# Kasli-SOC_bank33-34-35.net
KiCad netlist of a schematic drawn in Altium Designer
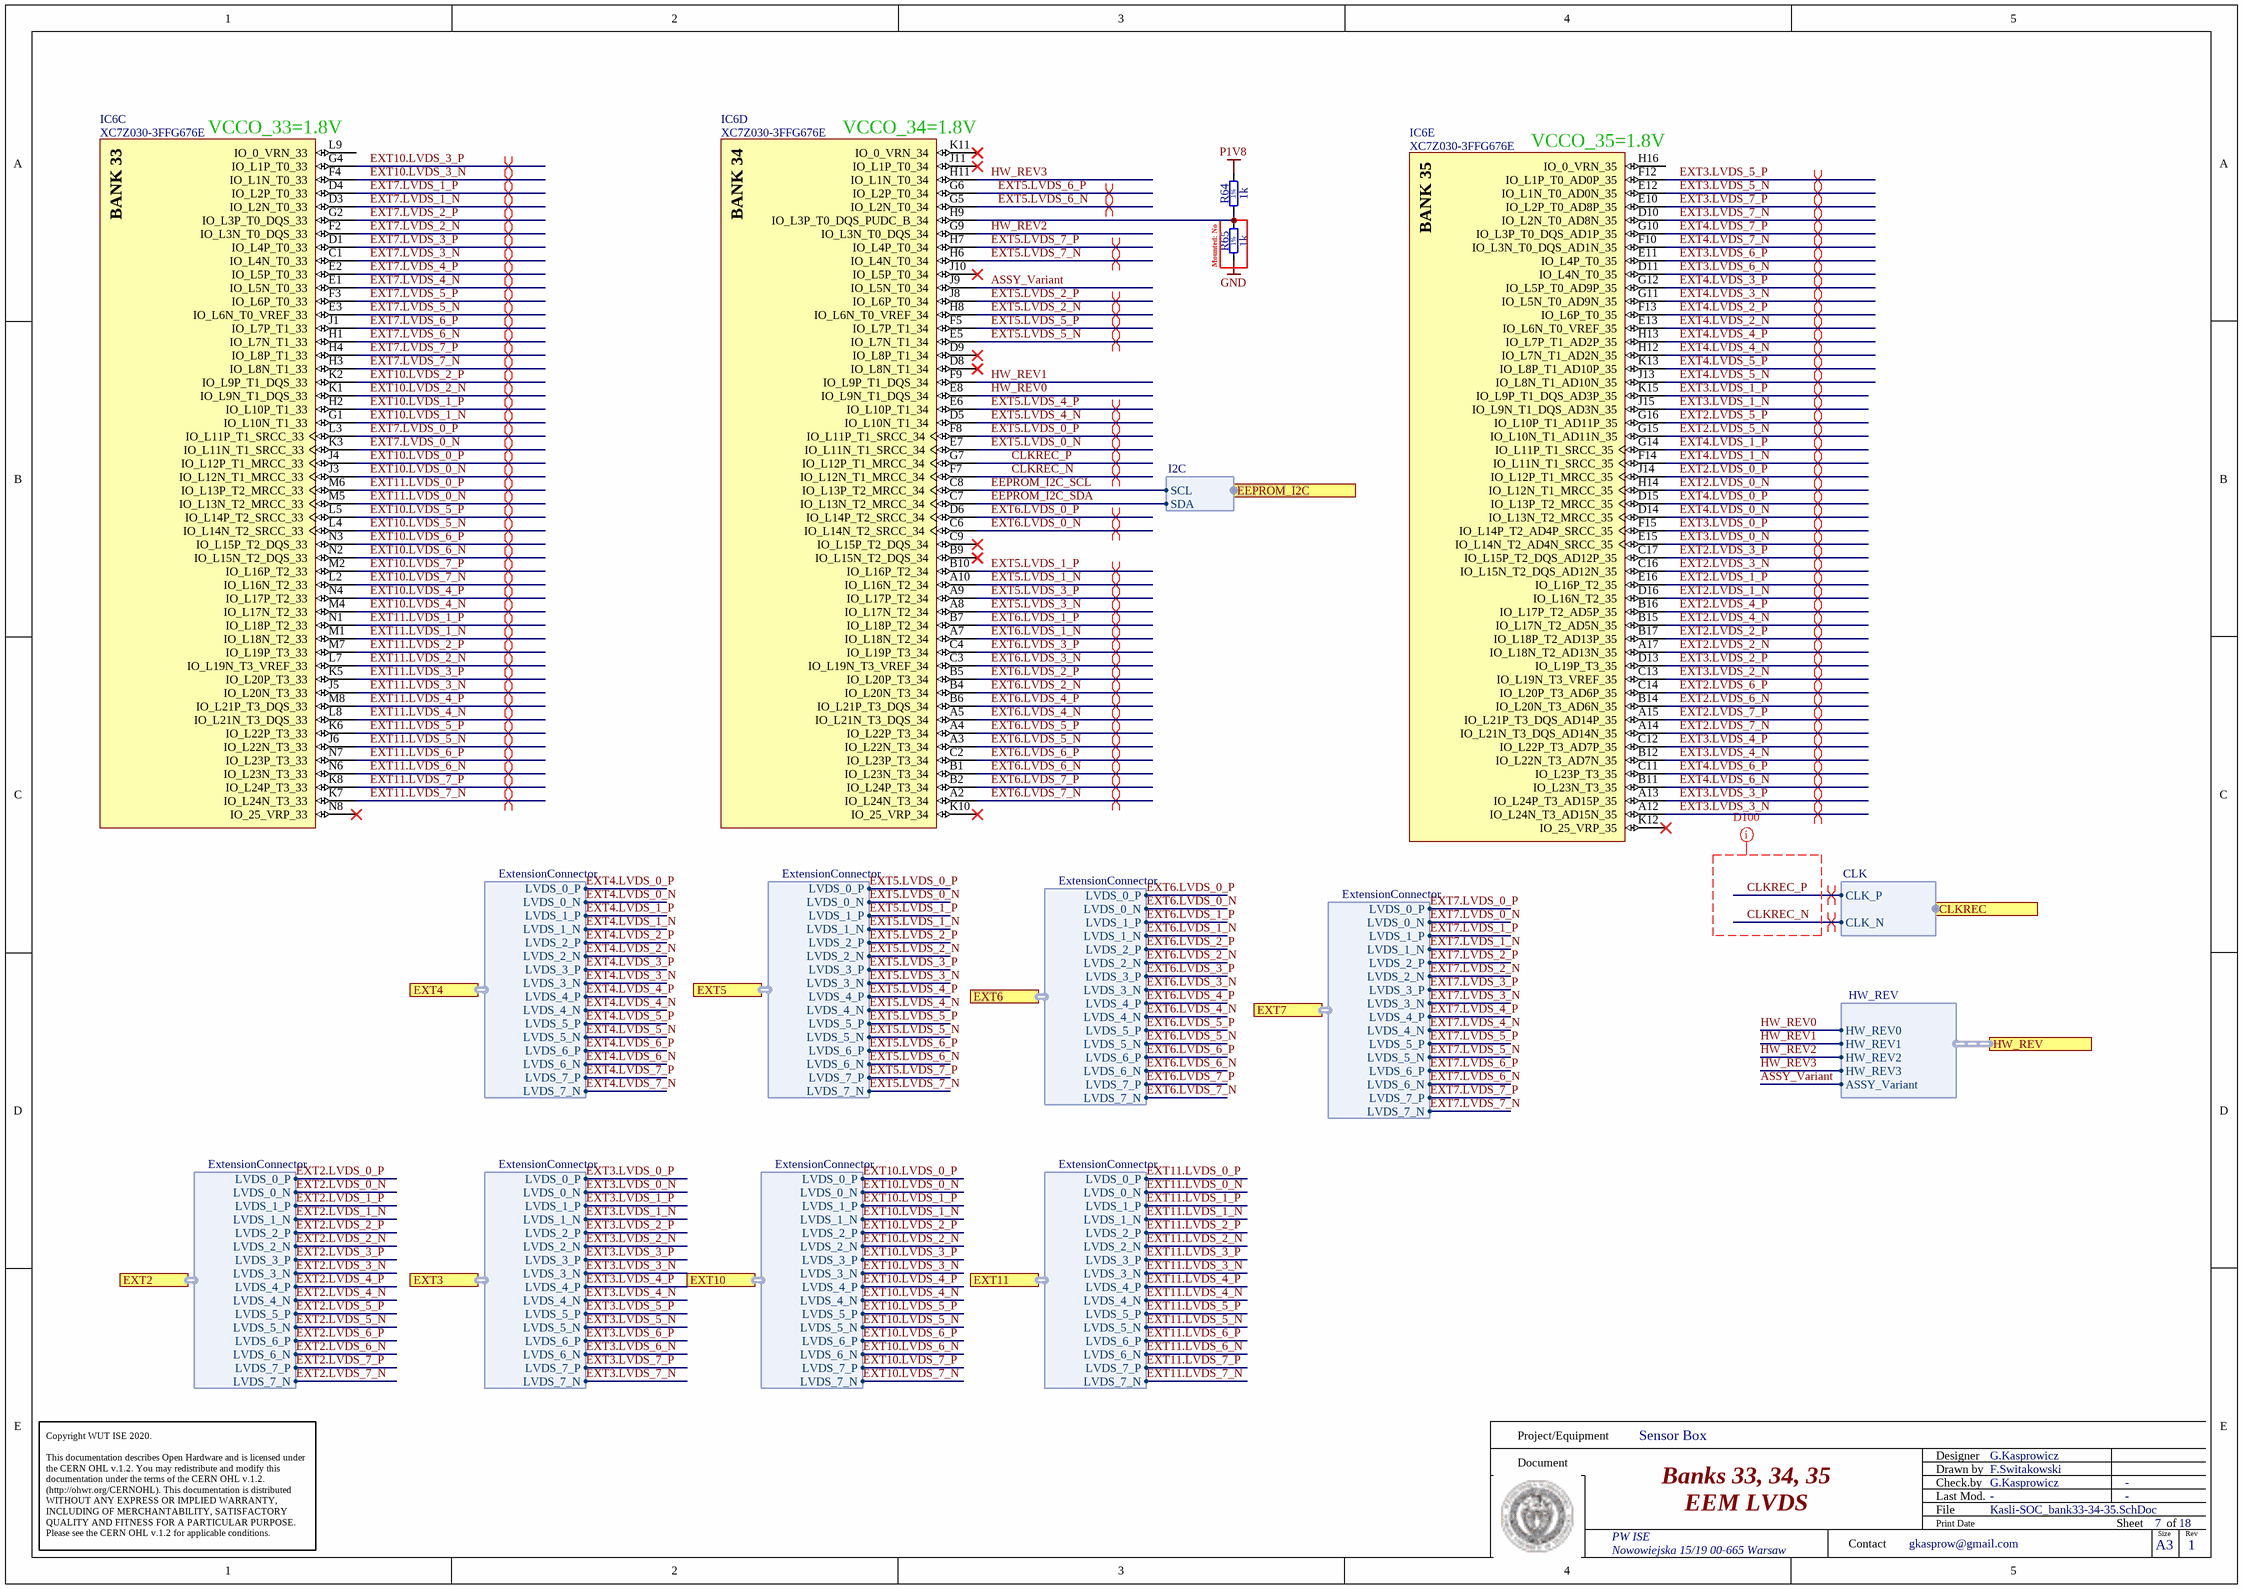
[diagram p0: Kasli-SOC_bank33-34-35.SchDoc]

(export (version "E")
  (design (tool "Eeschema 10.0.6"))
  (components
    (comp (ref "IC6")
      (value "XC7Z030-3FFG676E")
      (footprint "BGA676C100P26X26_2700X2700X324")
      (fields (field (name "MANUFACTURER") "XILINX") (field (name "AUTHOR") "CERN DEM JLC"))
      (libsource (lib "ICs And Semiconductors") (part "XC7Z030-2FFG676I"))
    )
    (comp (ref "R64")
      (value "1k")
      (footprint "RESC1005X40N")
      (description "Resistor - 1%")
      (fields
        (field (name "PART NUMBER") "R0402_1K_1%_0.0625W_100PPM")
        (field (name "POWER") "0.0625W")
        (field (name "AUTHOR") "CERN DEM JLC")
      )
      (libsource (lib "Resistors") (part "Resistor - 1%"))
    )
    (comp (ref "R65")
      (value "1k")
      (footprint "RESC1005X40N")
      (description "Resistor - 1%")
      (fields
        (field (name "PART NUMBER") "R0402_1K_1%_0.0625W_100PPM")
        (field (name "POWER") "0.0625W")
        (field (name "AUTHOR") "CERN DEM JLC")
      )
      (libsource (lib "Resistors") (part "Resistor - 1%"))
    )
  )
  (nets
    (net (code "5") (name "/ASSY_Variant") (class "Default")
      (node (ref "IC6") (pin "J9") (pinfunction "IO_L5N_T0_34_J9") (pintype "bidirectional"))
    )
    (net (code "6") (name "/CLKREC_N") (class "Default")
      (node (ref "IC6") (pin "F7") (pinfunction "IO_L12N_T1_MRCC_34_F7") (pintype "bidirectional"))
    )
    (net (code "7") (name "/CLKREC_P") (class "Default")
      (node (ref "IC6") (pin "G7") (pinfunction "IO_L12P_T1_MRCC_34_G7") (pintype "bidirectional"))
    )
    (net (code "8") (name "/EEPROM_I2C_SCL") (class "Default")
      (node (ref "IC6") (pin "C8") (pinfunction "IO_L13P_T2_MRCC_34_C8") (pintype "bidirectional"))
    )
    (net (code "9") (name "/EEPROM_I2C_SDA") (class "Default")
      (node (ref "IC6") (pin "C7") (pinfunction "IO_L13N_T2_MRCC_34_C7") (pintype "bidirectional"))
    )
    (net (code "10") (name "/EXT2.LVDS_0_N") (class "Default")
      (node (ref "IC6") (pin "H14") (pinfunction "IO_L12N_T1_MRCC_35_H14") (pintype "bidirectional"))
    )
    (net (code "11") (name "/EXT2.LVDS_0_P") (class "Default")
      (node (ref "IC6") (pin "J14") (pinfunction "IO_L12P_T1_MRCC_35_J14") (pintype "bidirectional"))
    )
    (net (code "12") (name "/EXT2.LVDS_1_N") (class "Default")
      (node (ref "IC6") (pin "D16") (pinfunction "IO_L16N_T2_35_D16") (pintype "bidirectional"))
    )
    (net (code "13") (name "/EXT2.LVDS_1_P") (class "Default")
      (node (ref "IC6") (pin "E16") (pinfunction "IO_L16P_T2_35_E16") (pintype "bidirectional"))
    )
    (net (code "14") (name "/EXT2.LVDS_2_N") (class "Default")
      (node (ref "IC6") (pin "A17") (pinfunction "IO_L18N_T2_AD13N_35_A17") (pintype "bidirectional"))
    )
    (net (code "15") (name "/EXT2.LVDS_2_P") (class "Default")
      (node (ref "IC6") (pin "B17") (pinfunction "IO_L18P_T2_AD13P_35_B17") (pintype "bidirectional"))
    )
    (net (code "16") (name "/EXT2.LVDS_3_N") (class "Default")
      (node (ref "IC6") (pin "C16") (pinfunction "IO_L15N_T2_DQS_AD12N_35_C16") (pintype "bidirectional"))
    )
    (net (code "17") (name "/EXT2.LVDS_3_P") (class "Default")
      (node (ref "IC6") (pin "C17") (pinfunction "IO_L15P_T2_DQS_AD12P_35_C17") (pintype "bidirectional"))
    )
    (net (code "18") (name "/EXT2.LVDS_4_N") (class "Default")
      (node (ref "IC6") (pin "B15") (pinfunction "IO_L17N_T2_AD5N_35_B15") (pintype "bidirectional"))
    )
    (net (code "19") (name "/EXT2.LVDS_4_P") (class "Default")
      (node (ref "IC6") (pin "B16") (pinfunction "IO_L17P_T2_AD5P_35_B16") (pintype "bidirectional"))
    )
    (net (code "20") (name "/EXT2.LVDS_5_N") (class "Default")
      (node (ref "IC6") (pin "G15") (pinfunction "IO_L10N_T1_AD11N_35_G15") (pintype "bidirectional"))
    )
    (net (code "21") (name "/EXT2.LVDS_5_P") (class "Default")
      (node (ref "IC6") (pin "G16") (pinfunction "IO_L10P_T1_AD11P_35_G16") (pintype "bidirectional"))
    )
    (net (code "22") (name "/EXT2.LVDS_6_N") (class "Default")
      (node (ref "IC6") (pin "B14") (pinfunction "IO_L20N_T3_AD6N_35_B14") (pintype "bidirectional"))
    )
    (net (code "23") (name "/EXT2.LVDS_6_P") (class "Default")
      (node (ref "IC6") (pin "C14") (pinfunction "IO_L20P_T3_AD6P_35_C14") (pintype "bidirectional"))
    )
    (net (code "24") (name "/EXT2.LVDS_7_N") (class "Default")
      (node (ref "IC6") (pin "A14") (pinfunction "IO_L21N_T3_DQS_AD14N_35_A14") (pintype "bidirectional"))
    )
    (net (code "25") (name "/EXT2.LVDS_7_P") (class "Default")
      (node (ref "IC6") (pin "A15") (pinfunction "IO_L21P_T3_DQS_AD14P_35_A15") (pintype "bidirectional"))
    )
    (net (code "26") (name "/EXT3.LVDS_0_N") (class "Default")
      (node (ref "IC6") (pin "E15") (pinfunction "IO_L14N_T2_AD4N_SRCC_35_E15") (pintype "bidirectional"))
    )
    (net (code "27") (name "/EXT3.LVDS_0_P") (class "Default")
      (node (ref "IC6") (pin "F15") (pinfunction "IO_L14P_T2_AD4P_SRCC_35_F15") (pintype "bidirectional"))
    )
    (net (code "28") (name "/EXT3.LVDS_1_N") (class "Default")
      (node (ref "IC6") (pin "J15") (pinfunction "IO_L9N_T1_DQS_AD3N_35_J15") (pintype "bidirectional"))
    )
    (net (code "29") (name "/EXT3.LVDS_1_P") (class "Default")
      (node (ref "IC6") (pin "K15") (pinfunction "IO_L9P_T1_DQS_AD3P_35_K15") (pintype "bidirectional"))
    )
    (net (code "30") (name "/EXT3.LVDS_2_N") (class "Default")
      (node (ref "IC6") (pin "C13") (pinfunction "IO_L19N_T3_VREF_35_C13") (pintype "bidirectional"))
    )
    (net (code "31") (name "/EXT3.LVDS_2_P") (class "Default")
      (node (ref "IC6") (pin "D13") (pinfunction "IO_L19P_T3_35_D13") (pintype "bidirectional"))
    )
    (net (code "32") (name "/EXT3.LVDS_3_N") (class "Default")
      (node (ref "IC6") (pin "A12") (pinfunction "IO_L24N_T3_AD15N_35_A12") (pintype "bidirectional"))
    )
    (net (code "33") (name "/EXT3.LVDS_3_P") (class "Default")
      (node (ref "IC6") (pin "A13") (pinfunction "IO_L24P_T3_AD15P_35_A13") (pintype "bidirectional"))
    )
    (net (code "34") (name "/EXT3.LVDS_4_N") (class "Default")
      (node (ref "IC6") (pin "B12") (pinfunction "IO_L22N_T3_AD7N_35_B12") (pintype "bidirectional"))
    )
    (net (code "35") (name "/EXT3.LVDS_4_P") (class "Default")
      (node (ref "IC6") (pin "C12") (pinfunction "IO_L22P_T3_AD7P_35_C12") (pintype "bidirectional"))
    )
    (net (code "36") (name "/EXT3.LVDS_5_N") (class "Default")
      (node (ref "IC6") (pin "E12") (pinfunction "IO_L1N_T0_AD0N_35_E12") (pintype "bidirectional"))
    )
    (net (code "37") (name "/EXT3.LVDS_5_P") (class "Default")
      (node (ref "IC6") (pin "F12") (pinfunction "IO_L1P_T0_AD0P_35_F12") (pintype "bidirectional"))
    )
    (net (code "38") (name "/EXT3.LVDS_6_N") (class "Default")
      (node (ref "IC6") (pin "D11") (pinfunction "IO_L4N_T0_35_D11") (pintype "bidirectional"))
    )
    (net (code "39") (name "/EXT3.LVDS_6_P") (class "Default")
      (node (ref "IC6") (pin "E11") (pinfunction "IO_L4P_T0_35_E11") (pintype "bidirectional"))
    )
    (net (code "40") (name "/EXT3.LVDS_7_N") (class "Default")
      (node (ref "IC6") (pin "D10") (pinfunction "IO_L2N_T0_AD8N_35_D10") (pintype "bidirectional"))
    )
    (net (code "41") (name "/EXT3.LVDS_7_P") (class "Default")
      (node (ref "IC6") (pin "E10") (pinfunction "IO_L2P_T0_AD8P_35_E10") (pintype "bidirectional"))
    )
    (net (code "42") (name "/EXT4.LVDS_0_N") (class "Default")
      (node (ref "IC6") (pin "D14") (pinfunction "IO_L13N_T2_MRCC_35_D14") (pintype "bidirectional"))
    )
    (net (code "43") (name "/EXT4.LVDS_0_P") (class "Default")
      (node (ref "IC6") (pin "D15") (pinfunction "IO_L13P_T2_MRCC_35_D15") (pintype "bidirectional"))
    )
    (net (code "44") (name "/EXT4.LVDS_1_N") (class "Default")
      (node (ref "IC6") (pin "F14") (pinfunction "IO_L11N_T1_SRCC_35_F14") (pintype "bidirectional"))
    )
    (net (code "45") (name "/EXT4.LVDS_1_P") (class "Default")
      (node (ref "IC6") (pin "G14") (pinfunction "IO_L11P_T1_SRCC_35_G14") (pintype "bidirectional"))
    )
    (net (code "46") (name "/EXT4.LVDS_2_N") (class "Default")
      (node (ref "IC6") (pin "E13") (pinfunction "IO_L6N_T0_VREF_35_E13") (pintype "bidirectional"))
    )
    (net (code "47") (name "/EXT4.LVDS_2_P") (class "Default")
      (node (ref "IC6") (pin "F13") (pinfunction "IO_L6P_T0_35_F13") (pintype "bidirectional"))
    )
    (net (code "48") (name "/EXT4.LVDS_3_N") (class "Default")
      (node (ref "IC6") (pin "G11") (pinfunction "IO_L5N_T0_AD9N_35_G11") (pintype "bidirectional"))
    )
    (net (code "49") (name "/EXT4.LVDS_3_P") (class "Default")
      (node (ref "IC6") (pin "G12") (pinfunction "IO_L5P_T0_AD9P_35_G12") (pintype "bidirectional"))
    )
    (net (code "50") (name "/EXT4.LVDS_4_N") (class "Default")
      (node (ref "IC6") (pin "H12") (pinfunction "IO_L7N_T1_AD2N_35_H12") (pintype "bidirectional"))
    )
    (net (code "51") (name "/EXT4.LVDS_4_P") (class "Default")
      (node (ref "IC6") (pin "H13") (pinfunction "IO_L7P_T1_AD2P_35_H13") (pintype "bidirectional"))
    )
    (net (code "52") (name "/EXT4.LVDS_5_N") (class "Default")
      (node (ref "IC6") (pin "J13") (pinfunction "IO_L8N_T1_AD10N_35_J13") (pintype "bidirectional"))
    )
    (net (code "53") (name "/EXT4.LVDS_5_P") (class "Default")
      (node (ref "IC6") (pin "K13") (pinfunction "IO_L8P_T1_AD10P_35_K13") (pintype "bidirectional"))
    )
    (net (code "54") (name "/EXT4.LVDS_6_N") (class "Default")
      (node (ref "IC6") (pin "B11") (pinfunction "IO_L23N_T3_35_B11") (pintype "bidirectional"))
    )
    (net (code "55") (name "/EXT4.LVDS_6_P") (class "Default")
      (node (ref "IC6") (pin "C11") (pinfunction "IO_L23P_T3_35_C11") (pintype "bidirectional"))
    )
    (net (code "56") (name "/EXT4.LVDS_7_N") (class "Default")
      (node (ref "IC6") (pin "F10") (pinfunction "IO_L3N_T0_DQS_AD1N_35_F10") (pintype "bidirectional"))
    )
    (net (code "57") (name "/EXT4.LVDS_7_P") (class "Default")
      (node (ref "IC6") (pin "G10") (pinfunction "IO_L3P_T0_DQS_AD1P_35_G10") (pintype "bidirectional"))
    )
    (net (code "58") (name "/EXT5.LVDS_0_N") (class "Default")
      (node (ref "IC6") (pin "E7") (pinfunction "IO_L11N_T1_SRCC_34_E7") (pintype "bidirectional"))
    )
    (net (code "59") (name "/EXT5.LVDS_0_P") (class "Default")
      (node (ref "IC6") (pin "F8") (pinfunction "IO_L11P_T1_SRCC_34_F8") (pintype "bidirectional"))
    )
    (net (code "60") (name "/EXT5.LVDS_1_N") (class "Default")
      (node (ref "IC6") (pin "A10") (pinfunction "IO_L16N_T2_34_A10") (pintype "bidirectional"))
    )
    (net (code "61") (name "/EXT5.LVDS_1_P") (class "Default")
      (node (ref "IC6") (pin "B10") (pinfunction "IO_L16P_T2_34_B10") (pintype "bidirectional"))
    )
    (net (code "62") (name "/EXT5.LVDS_2_N") (class "Default")
      (node (ref "IC6") (pin "H8") (pinfunction "IO_L6N_T0_VREF_34_H8") (pintype "bidirectional"))
    )
    (net (code "63") (name "/EXT5.LVDS_2_P") (class "Default")
      (node (ref "IC6") (pin "J8") (pinfunction "IO_L6P_T0_34_J8") (pintype "bidirectional"))
    )
    (net (code "64") (name "/EXT5.LVDS_3_N") (class "Default")
      (node (ref "IC6") (pin "A8") (pinfunction "IO_L17N_T2_34_A8") (pintype "bidirectional"))
    )
    (net (code "65") (name "/EXT5.LVDS_3_P") (class "Default")
      (node (ref "IC6") (pin "A9") (pinfunction "IO_L17P_T2_34_A9") (pintype "bidirectional"))
    )
    (net (code "66") (name "/EXT5.LVDS_4_N") (class "Default")
      (node (ref "IC6") (pin "D5") (pinfunction "IO_L10N_T1_34_D5") (pintype "bidirectional"))
    )
    (net (code "67") (name "/EXT5.LVDS_4_P") (class "Default")
      (node (ref "IC6") (pin "E6") (pinfunction "IO_L10P_T1_34_E6") (pintype "bidirectional"))
    )
    (net (code "68") (name "/EXT5.LVDS_5_N") (class "Default")
      (node (ref "IC6") (pin "E5") (pinfunction "IO_L7N_T1_34_E5") (pintype "bidirectional"))
    )
    (net (code "69") (name "/EXT5.LVDS_5_P") (class "Default")
      (node (ref "IC6") (pin "F5") (pinfunction "IO_L7P_T1_34_F5") (pintype "bidirectional"))
    )
    (net (code "70") (name "/EXT5.LVDS_6_N") (class "Default")
      (node (ref "IC6") (pin "G5") (pinfunction "IO_L2N_T0_34_G5") (pintype "bidirectional"))
    )
    (net (code "71") (name "/EXT5.LVDS_6_P") (class "Default")
      (node (ref "IC6") (pin "G6") (pinfunction "IO_L2P_T0_34_G6") (pintype "bidirectional"))
    )
    (net (code "72") (name "/EXT5.LVDS_7_N") (class "Default")
      (node (ref "IC6") (pin "H6") (pinfunction "IO_L4N_T0_34_H6") (pintype "bidirectional"))
    )
    (net (code "73") (name "/EXT5.LVDS_7_P") (class "Default")
      (node (ref "IC6") (pin "H7") (pinfunction "IO_L4P_T0_34_H7") (pintype "bidirectional"))
    )
    (net (code "74") (name "/EXT6.LVDS_0_N") (class "Default")
      (node (ref "IC6") (pin "C6") (pinfunction "IO_L14N_T2_SRCC_34_C6") (pintype "bidirectional"))
    )
    (net (code "75") (name "/EXT6.LVDS_0_P") (class "Default")
      (node (ref "IC6") (pin "D6") (pinfunction "IO_L14P_T2_SRCC_34_D6") (pintype "bidirectional"))
    )
    (net (code "76") (name "/EXT6.LVDS_1_N") (class "Default")
      (node (ref "IC6") (pin "A7") (pinfunction "IO_L18N_T2_34_A7") (pintype "bidirectional"))
    )
    (net (code "77") (name "/EXT6.LVDS_1_P") (class "Default")
      (node (ref "IC6") (pin "B7") (pinfunction "IO_L18P_T2_34_B7") (pintype "bidirectional"))
    )
    (net (code "78") (name "/EXT6.LVDS_2_N") (class "Default")
      (node (ref "IC6") (pin "B4") (pinfunction "IO_L20N_T3_34_B4") (pintype "bidirectional"))
    )
    (net (code "79") (name "/EXT6.LVDS_2_P") (class "Default")
      (node (ref "IC6") (pin "B5") (pinfunction "IO_L20P_T3_34_B5") (pintype "bidirectional"))
    )
    (net (code "80") (name "/EXT6.LVDS_3_N") (class "Default")
      (node (ref "IC6") (pin "C3") (pinfunction "IO_L19N_T3_VREF_34_C3") (pintype "bidirectional"))
    )
    (net (code "81") (name "/EXT6.LVDS_3_P") (class "Default")
      (node (ref "IC6") (pin "C4") (pinfunction "IO_L19P_T3_34_C4") (pintype "bidirectional"))
    )
    (net (code "82") (name "/EXT6.LVDS_4_N") (class "Default")
      (node (ref "IC6") (pin "A5") (pinfunction "IO_L21N_T3_DQS_34_A5") (pintype "bidirectional"))
    )
    (net (code "83") (name "/EXT6.LVDS_4_P") (class "Default")
      (node (ref "IC6") (pin "B6") (pinfunction "IO_L21P_T3_DQS_34_B6") (pintype "bidirectional"))
    )
    (net (code "84") (name "/EXT6.LVDS_5_N") (class "Default")
      (node (ref "IC6") (pin "A3") (pinfunction "IO_L22N_T3_34_A3") (pintype "bidirectional"))
    )
    (net (code "85") (name "/EXT6.LVDS_5_P") (class "Default")
      (node (ref "IC6") (pin "A4") (pinfunction "IO_L22P_T3_34_A4") (pintype "bidirectional"))
    )
    (net (code "86") (name "/EXT6.LVDS_6_N") (class "Default")
      (node (ref "IC6") (pin "B1") (pinfunction "IO_L23N_T3_34_B1") (pintype "bidirectional"))
    )
    (net (code "87") (name "/EXT6.LVDS_6_P") (class "Default")
      (node (ref "IC6") (pin "C2") (pinfunction "IO_L23P_T3_34_C2") (pintype "bidirectional"))
    )
    (net (code "88") (name "/EXT6.LVDS_7_N") (class "Default")
      (node (ref "IC6") (pin "A2") (pinfunction "IO_L24N_T3_34_A2") (pintype "bidirectional"))
    )
    (net (code "89") (name "/EXT6.LVDS_7_P") (class "Default")
      (node (ref "IC6") (pin "B2") (pinfunction "IO_L24P_T3_34_B2") (pintype "bidirectional"))
    )
    (net (code "90") (name "/EXT7.LVDS_0_N") (class "Default")
      (node (ref "IC6") (pin "K3") (pinfunction "IO_L11N_T1_SRCC_33_K3") (pintype "bidirectional"))
    )
    (net (code "91") (name "/EXT7.LVDS_0_P") (class "Default")
      (node (ref "IC6") (pin "L3") (pinfunction "IO_L11P_T1_SRCC_33_L3") (pintype "bidirectional"))
    )
    (net (code "92") (name "/EXT7.LVDS_1_N") (class "Default")
      (node (ref "IC6") (pin "D3") (pinfunction "IO_L2N_T0_33_D3") (pintype "bidirectional"))
    )
    (net (code "93") (name "/EXT7.LVDS_1_P") (class "Default")
      (node (ref "IC6") (pin "D4") (pinfunction "IO_L2P_T0_33_D4") (pintype "bidirectional"))
    )
    (net (code "94") (name "/EXT7.LVDS_2_N") (class "Default")
      (node (ref "IC6") (pin "F2") (pinfunction "IO_L3N_T0_DQS_33_F2") (pintype "bidirectional"))
    )
    (net (code "95") (name "/EXT7.LVDS_2_P") (class "Default")
      (node (ref "IC6") (pin "G2") (pinfunction "IO_L3P_T0_DQS_33_G2") (pintype "bidirectional"))
    )
    (net (code "96") (name "/EXT7.LVDS_3_N") (class "Default")
      (node (ref "IC6") (pin "C1") (pinfunction "IO_L4N_T0_33_C1") (pintype "bidirectional"))
    )
    (net (code "97") (name "/EXT7.LVDS_3_P") (class "Default")
      (node (ref "IC6") (pin "D1") (pinfunction "IO_L4P_T0_33_D1") (pintype "bidirectional"))
    )
    (net (code "98") (name "/EXT7.LVDS_4_N") (class "Default")
      (node (ref "IC6") (pin "E1") (pinfunction "IO_L5N_T0_33_E1") (pintype "bidirectional"))
    )
    (net (code "99") (name "/EXT7.LVDS_4_P") (class "Default")
      (node (ref "IC6") (pin "E2") (pinfunction "IO_L5P_T0_33_E2") (pintype "bidirectional"))
    )
    (net (code "100") (name "/EXT7.LVDS_5_N") (class "Default")
      (node (ref "IC6") (pin "E3") (pinfunction "IO_L6N_T0_VREF_33_E3") (pintype "bidirectional"))
    )
    (net (code "101") (name "/EXT7.LVDS_5_P") (class "Default")
      (node (ref "IC6") (pin "F3") (pinfunction "IO_L6P_T0_33_F3") (pintype "bidirectional"))
    )
    (net (code "102") (name "/EXT7.LVDS_6_N") (class "Default")
      (node (ref "IC6") (pin "H1") (pinfunction "IO_L7N_T1_33_H1") (pintype "bidirectional"))
    )
    (net (code "103") (name "/EXT7.LVDS_6_P") (class "Default")
      (node (ref "IC6") (pin "J1") (pinfunction "IO_L7P_T1_33_J1") (pintype "bidirectional"))
    )
    (net (code "104") (name "/EXT7.LVDS_7_N") (class "Default")
      (node (ref "IC6") (pin "H3") (pinfunction "IO_L8N_T1_33_H3") (pintype "bidirectional"))
    )
    (net (code "105") (name "/EXT7.LVDS_7_P") (class "Default")
      (node (ref "IC6") (pin "H4") (pinfunction "IO_L8P_T1_33_H4") (pintype "bidirectional"))
    )
    (net (code "106") (name "/EXT10.LVDS_0_N") (class "Default")
      (node (ref "IC6") (pin "J3") (pinfunction "IO_L12N_T1_MRCC_33_J3") (pintype "bidirectional"))
    )
    (net (code "107") (name "/EXT10.LVDS_0_P") (class "Default")
      (node (ref "IC6") (pin "J4") (pinfunction "IO_L12P_T1_MRCC_33_J4") (pintype "bidirectional"))
    )
    (net (code "108") (name "/EXT10.LVDS_1_N") (class "Default")
      (node (ref "IC6") (pin "G1") (pinfunction "IO_L10N_T1_33_G1") (pintype "bidirectional"))
    )
    (net (code "109") (name "/EXT10.LVDS_1_P") (class "Default")
      (node (ref "IC6") (pin "H2") (pinfunction "IO_L10P_T1_33_H2") (pintype "bidirectional"))
    )
    (net (code "110") (name "/EXT10.LVDS_2_N") (class "Default")
      (node (ref "IC6") (pin "K1") (pinfunction "IO_L9N_T1_DQS_33_K1") (pintype "bidirectional"))
    )
    (net (code "111") (name "/EXT10.LVDS_2_P") (class "Default")
      (node (ref "IC6") (pin "K2") (pinfunction "IO_L9P_T1_DQS_33_K2") (pintype "bidirectional"))
    )
    (net (code "112") (name "/EXT10.LVDS_3_N") (class "Default")
      (node (ref "IC6") (pin "F4") (pinfunction "IO_L1N_T0_33_F4") (pintype "bidirectional"))
    )
    (net (code "113") (name "/EXT10.LVDS_3_P") (class "Default")
      (node (ref "IC6") (pin "G4") (pinfunction "IO_L1P_T0_33_G4") (pintype "bidirectional"))
    )
    (net (code "114") (name "/EXT10.LVDS_4_N") (class "Default")
      (node (ref "IC6") (pin "M4") (pinfunction "IO_L17N_T2_33_M4") (pintype "bidirectional"))
    )
    (net (code "115") (name "/EXT10.LVDS_4_P") (class "Default")
      (node (ref "IC6") (pin "N4") (pinfunction "IO_L17P_T2_33_N4") (pintype "bidirectional"))
    )
    (net (code "116") (name "/EXT10.LVDS_5_N") (class "Default")
      (node (ref "IC6") (pin "L4") (pinfunction "IO_L14N_T2_SRCC_33_L4") (pintype "bidirectional"))
    )
    (net (code "117") (name "/EXT10.LVDS_5_P") (class "Default")
      (node (ref "IC6") (pin "L5") (pinfunction "IO_L14P_T2_SRCC_33_L5") (pintype "bidirectional"))
    )
    (net (code "118") (name "/EXT10.LVDS_6_N") (class "Default")
      (node (ref "IC6") (pin "N2") (pinfunction "IO_L15N_T2_DQS_33_N2") (pintype "bidirectional"))
    )
    (net (code "119") (name "/EXT10.LVDS_6_P") (class "Default")
      (node (ref "IC6") (pin "N3") (pinfunction "IO_L15P_T2_DQS_33_N3") (pintype "bidirectional"))
    )
    (net (code "120") (name "/EXT10.LVDS_7_N") (class "Default")
      (node (ref "IC6") (pin "L2") (pinfunction "IO_L16N_T2_33_L2") (pintype "bidirectional"))
    )
    (net (code "121") (name "/EXT10.LVDS_7_P") (class "Default")
      (node (ref "IC6") (pin "M2") (pinfunction "IO_L16P_T2_33_M2") (pintype "bidirectional"))
    )
    (net (code "122") (name "/EXT11.LVDS_0_N") (class "Default")
      (node (ref "IC6") (pin "M5") (pinfunction "IO_L13N_T2_MRCC_33_M5") (pintype "bidirectional"))
    )
    (net (code "123") (name "/EXT11.LVDS_0_P") (class "Default")
      (node (ref "IC6") (pin "M6") (pinfunction "IO_L13P_T2_MRCC_33_M6") (pintype "bidirectional"))
    )
    (net (code "124") (name "/EXT11.LVDS_1_N") (class "Default")
      (node (ref "IC6") (pin "M1") (pinfunction "IO_L18N_T2_33_M1") (pintype "bidirectional"))
    )
    (net (code "125") (name "/EXT11.LVDS_1_P") (class "Default")
      (node (ref "IC6") (pin "N1") (pinfunction "IO_L18P_T2_33_N1") (pintype "bidirectional"))
    )
    (net (code "126") (name "/EXT11.LVDS_2_N") (class "Default")
      (node (ref "IC6") (pin "L7") (pinfunction "IO_L19N_T3_VREF_33_L7") (pintype "bidirectional"))
    )
    (net (code "127") (name "/EXT11.LVDS_2_P") (class "Default")
      (node (ref "IC6") (pin "M7") (pinfunction "IO_L19P_T3_33_M7") (pintype "bidirectional"))
    )
    (net (code "128") (name "/EXT11.LVDS_3_N") (class "Default")
      (node (ref "IC6") (pin "J5") (pinfunction "IO_L20N_T3_33_J5") (pintype "bidirectional"))
    )
    (net (code "129") (name "/EXT11.LVDS_3_P") (class "Default")
      (node (ref "IC6") (pin "K5") (pinfunction "IO_L20P_T3_33_K5") (pintype "bidirectional"))
    )
    (net (code "130") (name "/EXT11.LVDS_4_N") (class "Default")
      (node (ref "IC6") (pin "L8") (pinfunction "IO_L21N_T3_DQS_33_L8") (pintype "bidirectional"))
    )
    (net (code "131") (name "/EXT11.LVDS_4_P") (class "Default")
      (node (ref "IC6") (pin "M8") (pinfunction "IO_L21P_T3_DQS_33_M8") (pintype "bidirectional"))
    )
    (net (code "132") (name "/EXT11.LVDS_5_N") (class "Default")
      (node (ref "IC6") (pin "J6") (pinfunction "IO_L22N_T3_33_J6") (pintype "bidirectional"))
    )
    (net (code "133") (name "/EXT11.LVDS_5_P") (class "Default")
      (node (ref "IC6") (pin "K6") (pinfunction "IO_L22P_T3_33_K6") (pintype "bidirectional"))
    )
    (net (code "134") (name "/EXT11.LVDS_6_N") (class "Default")
      (node (ref "IC6") (pin "N6") (pinfunction "IO_L23N_T3_33_N6") (pintype "bidirectional"))
    )
    (net (code "135") (name "/EXT11.LVDS_6_P") (class "Default")
      (node (ref "IC6") (pin "N7") (pinfunction "IO_L23P_T3_33_N7") (pintype "bidirectional"))
    )
    (net (code "136") (name "/EXT11.LVDS_7_N") (class "Default")
      (node (ref "IC6") (pin "K7") (pinfunction "IO_L24N_T3_33_K7") (pintype "bidirectional"))
    )
    (net (code "137") (name "/EXT11.LVDS_7_P") (class "Default")
      (node (ref "IC6") (pin "K8") (pinfunction "IO_L24P_T3_33_K8") (pintype "bidirectional"))
    )
    (net (code "138") (name "/HW_REV0") (class "Default")
      (node (ref "IC6") (pin "E8") (pinfunction "IO_L9N_T1_DQS_34_E8") (pintype "bidirectional"))
    )
    (net (code "139") (name "/HW_REV1") (class "Default")
      (node (ref "IC6") (pin "F9") (pinfunction "IO_L9P_T1_DQS_34_F9") (pintype "bidirectional"))
    )
    (net (code "140") (name "/HW_REV2") (class "Default")
      (node (ref "IC6") (pin "G9") (pinfunction "IO_L3N_T0_DQS_34_G9") (pintype "bidirectional"))
    )
    (net (code "141") (name "/HW_REV3") (class "Default")
      (node (ref "IC6") (pin "H11") (pinfunction "IO_L1N_T0_34_H11") (pintype "bidirectional"))
    )
    (net (code "146") (name "GND") (class "Default")
      (node (ref "R65") (pin "1") (pinfunction "1_1") (pintype "passive"))
    )
    (net (code "147") (name "Net-(IC6D-IO_L3P_T0_DQS_PUDC_B_34)") (class "Default")
      (node (ref "IC6") (pin "H9") (pinfunction "IO_L3P_T0_DQS_PUDC_B_34_H9") (pintype "bidirectional"))
      (node (ref "R64") (pin "1") (pinfunction "1_1") (pintype "passive"))
      (node (ref "R65") (pin "2") (pinfunction "2_2") (pintype "passive"))
    )
    (net (code "148") (name "P1V8") (class "Default")
      (node (ref "R64") (pin "2") (pinfunction "2_2") (pintype "passive"))
    )
    (net (code "149") (name "unconnected-(IC6C-IO_0_VRN_33-PadL9)") (class "Default")
      (node (ref "IC6") (pin "L9") (pinfunction "IO_0_VRN_33_L9") (pintype "bidirectional"))
    )
    (net (code "150") (name "unconnected-(IC6C-IO_25_VRP_33-PadN8)") (class "Default")
      (node (ref "IC6") (pin "N8") (pinfunction "IO_25_VRP_33_N8") (pintype "bidirectional+no_connect"))
    )
    (net (code "151") (name "unconnected-(IC6D-IO_0_VRN_34-PadK11)") (class "Default")
      (node (ref "IC6") (pin "K11") (pinfunction "IO_0_VRN_34_K11") (pintype "bidirectional+no_connect"))
    )
    (net (code "152") (name "unconnected-(IC6D-IO_25_VRP_34-PadK10)") (class "Default")
      (node (ref "IC6") (pin "K10") (pinfunction "IO_25_VRP_34_K10") (pintype "bidirectional+no_connect"))
    )
    (net (code "153") (name "unconnected-(IC6D-IO_L1P_T0_34-PadJ11)") (class "Default")
      (node (ref "IC6") (pin "J11") (pinfunction "IO_L1P_T0_34_J11") (pintype "bidirectional+no_connect"))
    )
    (net (code "154") (name "unconnected-(IC6D-IO_L5P_T0_34-PadJ10)") (class "Default")
      (node (ref "IC6") (pin "J10") (pinfunction "IO_L5P_T0_34_J10") (pintype "bidirectional+no_connect"))
    )
    (net (code "155") (name "unconnected-(IC6D-IO_L8N_T1_34-PadD8)") (class "Default")
      (node (ref "IC6") (pin "D8") (pinfunction "IO_L8N_T1_34_D8") (pintype "bidirectional+no_connect"))
    )
    (net (code "156") (name "unconnected-(IC6D-IO_L8P_T1_34-PadD9)") (class "Default")
      (node (ref "IC6") (pin "D9") (pinfunction "IO_L8P_T1_34_D9") (pintype "bidirectional+no_connect"))
    )
    (net (code "157") (name "unconnected-(IC6D-IO_L15N_T2_DQS_34-PadB9)") (class "Default")
      (node (ref "IC6") (pin "B9") (pinfunction "IO_L15N_T2_DQS_34_B9") (pintype "bidirectional+no_connect"))
    )
    (net (code "158") (name "unconnected-(IC6D-IO_L15P_T2_DQS_34-PadC9)") (class "Default")
      (node (ref "IC6") (pin "C9") (pinfunction "IO_L15P_T2_DQS_34_C9") (pintype "bidirectional+no_connect"))
    )
    (net (code "159") (name "unconnected-(IC6E-IO_0_VRN_35-PadH16)") (class "Default")
      (node (ref "IC6") (pin "H16") (pinfunction "IO_0_VRN_35_H16") (pintype "bidirectional"))
    )
    (net (code "160") (name "unconnected-(IC6E-IO_25_VRP_35-PadK12)") (class "Default")
      (node (ref "IC6") (pin "K12") (pinfunction "IO_25_VRP_35_K12") (pintype "bidirectional+no_connect"))
    )
  )
)
